# schematics.net
KiCad netlist of a schematic drawn in EAGLE
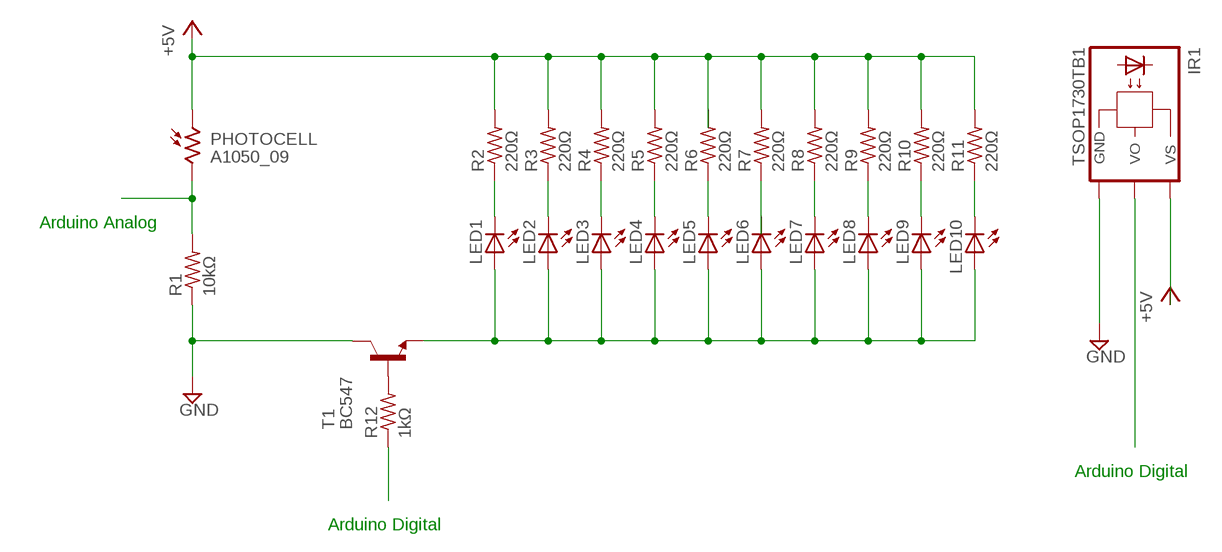
[diagram p0: schematic, sheet 1]

(export (version "E")
  (design (tool "Eeschema 10.0.6"))
  (components
    (comp (ref "IR1")
      (value "TSOP1730TB1")
      (footprint "eagle-import:TSOP17_TB1")
      (libsource (lib "eagle-import") (part "TSOP17TB130"))
    )
    (comp (ref "LED1")
      (value "LED5MM")
      (footprint "eagle-import:LED5MM")
      (libsource (lib "eagle-import") (part "LED5MM"))
    )
    (comp (ref "LED2")
      (value "LED5MM")
      (footprint "eagle-import:LED5MM")
      (libsource (lib "eagle-import") (part "LED5MM"))
    )
    (comp (ref "LED3")
      (value "LED5MM")
      (footprint "eagle-import:LED5MM")
      (libsource (lib "eagle-import") (part "LED5MM"))
    )
    (comp (ref "LED4")
      (value "LED5MM")
      (footprint "eagle-import:LED5MM")
      (libsource (lib "eagle-import") (part "LED5MM"))
    )
    (comp (ref "LED5")
      (value "LED5MM")
      (footprint "eagle-import:LED5MM")
      (libsource (lib "eagle-import") (part "LED5MM"))
    )
    (comp (ref "LED6")
      (value "LED5MM")
      (footprint "eagle-import:LED5MM")
      (libsource (lib "eagle-import") (part "LED5MM"))
    )
    (comp (ref "LED7")
      (value "LED5MM")
      (footprint "eagle-import:LED5MM")
      (libsource (lib "eagle-import") (part "LED5MM"))
    )
    (comp (ref "LED8")
      (value "LED5MM")
      (footprint "eagle-import:LED5MM")
      (libsource (lib "eagle-import") (part "LED5MM"))
    )
    (comp (ref "LED9")
      (value "LED5MM")
      (footprint "eagle-import:LED5MM")
      (libsource (lib "eagle-import") (part "LED5MM"))
    )
    (comp (ref "LED10")
      (value "LED5MM")
      (footprint "eagle-import:LED5MM")
      (libsource (lib "eagle-import") (part "LED5MM"))
    )
    (comp (ref "PHOTOCELL")
      (value "A1050_09")
      (footprint "eagle-import:T0-46-A10XX")
      (libsource (lib "eagle-import") (part "A1050_09"))
    )
    (comp (ref "R1")
      (value "10kΩ")
      (footprint "eagle-import:0204_5")
      (libsource (lib "eagle-import") (part "R-US_0204/5"))
    )
    (comp (ref "R2")
      (value "220Ω")
      (footprint "eagle-import:0204_5")
      (libsource (lib "eagle-import") (part "R-US_0204/5"))
    )
    (comp (ref "R3")
      (value "220Ω")
      (footprint "eagle-import:0204_5")
      (libsource (lib "eagle-import") (part "R-US_0204/5"))
    )
    (comp (ref "R4")
      (value "220Ω")
      (footprint "eagle-import:0204_5")
      (libsource (lib "eagle-import") (part "R-US_0204/5"))
    )
    (comp (ref "R5")
      (value "220Ω")
      (footprint "eagle-import:0204_5")
      (libsource (lib "eagle-import") (part "R-US_0204/5"))
    )
    (comp (ref "R6")
      (value "220Ω")
      (footprint "eagle-import:0204_5")
      (libsource (lib "eagle-import") (part "R-US_0204/5"))
    )
    (comp (ref "R7")
      (value "220Ω")
      (footprint "eagle-import:0204_5")
      (libsource (lib "eagle-import") (part "R-US_0204/5"))
    )
    (comp (ref "R8")
      (value "220Ω")
      (footprint "eagle-import:0204_5")
      (libsource (lib "eagle-import") (part "R-US_0204/5"))
    )
    (comp (ref "R9")
      (value "220Ω")
      (footprint "eagle-import:0204_5")
      (libsource (lib "eagle-import") (part "R-US_0204/5"))
    )
    (comp (ref "R10")
      (value "220Ω")
      (footprint "eagle-import:0204_5")
      (libsource (lib "eagle-import") (part "R-US_0204/5"))
    )
    (comp (ref "R11")
      (value "220Ω")
      (footprint "eagle-import:0204_5")
      (libsource (lib "eagle-import") (part "R-US_0204/5"))
    )
    (comp (ref "R12")
      (value "1kΩ")
      (footprint "eagle-import:0204_5")
      (libsource (lib "eagle-import") (part "R-US_0204/5"))
    )
    (comp (ref "T1")
      (value "BC547")
      (footprint "eagle-import:TO92")
      (libsource (lib "eagle-import") (part "BC547"))
    )
  )
  (nets
    (net (code "1") (name "+5V") (class "Default")
      (node (ref "IR1") (pin "VS") (pinfunction "VS_VS") (pintype "power_in"))
      (node (ref "PHOTOCELL") (pin "1") (pinfunction "1_1") (pintype "passive"))
      (node (ref "R10") (pin "2") (pinfunction "2_2") (pintype "passive"))
      (node (ref "R11") (pin "2") (pinfunction "2_2") (pintype "passive"))
      (node (ref "R2") (pin "2") (pinfunction "2_2") (pintype "passive"))
      (node (ref "R3") (pin "2") (pinfunction "2_2") (pintype "passive"))
      (node (ref "R4") (pin "2") (pinfunction "2_2") (pintype "passive"))
      (node (ref "R5") (pin "2") (pinfunction "2_2") (pintype "passive"))
      (node (ref "R7") (pin "2") (pinfunction "2_2") (pintype "passive"))
      (node (ref "R8") (pin "2") (pinfunction "2_2") (pintype "passive"))
      (node (ref "R9") (pin "2") (pinfunction "2_2") (pintype "passive"))
    )
    (net (code "2") (name "GND") (class "Default")
      (node (ref "IR1") (pin "GND") (pinfunction "GND_GND") (pintype "power_in"))
      (node (ref "R1") (pin "1") (pinfunction "1_1") (pintype "passive"))
      (node (ref "T1") (pin "3") (pinfunction "C_3") (pintype "passive"))
    )
    (net (code "3") (name "Net-(LED1-C)") (class "Default")
      (node (ref "LED1") (pin "K") (pinfunction "C_K") (pintype "passive"))
      (node (ref "R2") (pin "1") (pinfunction "1_1") (pintype "passive"))
    )
    (net (code "4") (name "Net-(LED2-C)") (class "Default")
      (node (ref "LED2") (pin "K") (pinfunction "C_K") (pintype "passive"))
      (node (ref "R3") (pin "1") (pinfunction "1_1") (pintype "passive"))
    )
    (net (code "5") (name "Net-(LED3-C)") (class "Default")
      (node (ref "LED3") (pin "K") (pinfunction "C_K") (pintype "passive"))
      (node (ref "R4") (pin "1") (pinfunction "1_1") (pintype "passive"))
    )
    (net (code "6") (name "Net-(LED4-C)") (class "Default")
      (node (ref "LED4") (pin "K") (pinfunction "C_K") (pintype "passive"))
      (node (ref "R5") (pin "1") (pinfunction "1_1") (pintype "passive"))
    )
    (net (code "7") (name "Net-(LED5-C)") (class "Default")
      (node (ref "LED5") (pin "K") (pinfunction "C_K") (pintype "passive"))
      (node (ref "R6") (pin "1") (pinfunction "1_1") (pintype "passive"))
    )
    (net (code "8") (name "Net-(LED7-C)") (class "Default")
      (node (ref "LED7") (pin "K") (pinfunction "C_K") (pintype "passive"))
      (node (ref "R8") (pin "1") (pinfunction "1_1") (pintype "passive"))
    )
    (net (code "9") (name "Net-(LED8-C)") (class "Default")
      (node (ref "LED8") (pin "K") (pinfunction "C_K") (pintype "passive"))
      (node (ref "R9") (pin "1") (pinfunction "1_1") (pintype "passive"))
    )
    (net (code "10") (name "Net-(LED9-C)") (class "Default")
      (node (ref "LED9") (pin "K") (pinfunction "C_K") (pintype "passive"))
      (node (ref "R10") (pin "1") (pinfunction "1_1") (pintype "passive"))
    )
    (net (code "11") (name "Net-(LED10-C)") (class "Default")
      (node (ref "LED10") (pin "K") (pinfunction "C_K") (pintype "passive"))
      (node (ref "R11") (pin "1") (pinfunction "1_1") (pintype "passive"))
    )
    (net (code "12") (name "Net-(PHOTOCELL-Pad2)") (class "Default")
      (node (ref "PHOTOCELL") (pin "2") (pinfunction "2_2") (pintype "passive"))
      (node (ref "R1") (pin "2") (pinfunction "2_2") (pintype "passive"))
    )
    (net (code "13") (name "Net-(T1-B)") (class "Default")
      (node (ref "R12") (pin "2") (pinfunction "2_2") (pintype "passive"))
      (node (ref "T1") (pin "2") (pinfunction "B_2") (pintype "passive"))
    )
    (net (code "14") (name "Net-(T1-E)") (class "Default")
      (node (ref "LED1") (pin "A") (pinfunction "A_A") (pintype "passive"))
      (node (ref "LED10") (pin "A") (pinfunction "A_A") (pintype "passive"))
      (node (ref "LED2") (pin "A") (pinfunction "A_A") (pintype "passive"))
      (node (ref "LED3") (pin "A") (pinfunction "A_A") (pintype "passive"))
      (node (ref "LED4") (pin "A") (pinfunction "A_A") (pintype "passive"))
      (node (ref "LED5") (pin "A") (pinfunction "A_A") (pintype "passive"))
      (node (ref "LED6") (pin "A") (pinfunction "A_A") (pintype "passive"))
      (node (ref "LED7") (pin "A") (pinfunction "A_A") (pintype "passive"))
      (node (ref "LED8") (pin "A") (pinfunction "A_A") (pintype "passive"))
      (node (ref "LED9") (pin "A") (pinfunction "A_A") (pintype "passive"))
      (node (ref "T1") (pin "1") (pinfunction "E_1") (pintype "passive"))
    )
    (net (code "15") (name "unconnected-(IR1-PadVO)") (class "Default")
      (node (ref "IR1") (pin "VO") (pinfunction "VO_VO") (pintype "open_collector"))
    )
    (net (code "16") (name "unconnected-(LED6-C-PadK)") (class "Default")
      (node (ref "LED6") (pin "K") (pinfunction "C_K") (pintype "passive"))
    )
    (net (code "17") (name "unconnected-(R6-Pad2)") (class "Default")
      (node (ref "R6") (pin "2") (pinfunction "2_2") (pintype "passive"))
    )
    (net (code "18") (name "unconnected-(R7-Pad1)") (class "Default")
      (node (ref "R7") (pin "1") (pinfunction "1_1") (pintype "passive"))
    )
    (net (code "19") (name "unconnected-(R12-Pad1)") (class "Default")
      (node (ref "R12") (pin "1") (pinfunction "1_1") (pintype "passive"))
    )
  )
)
